# IOIO-OTG-v20.net
KiCad netlist of a schematic drawn in EAGLE
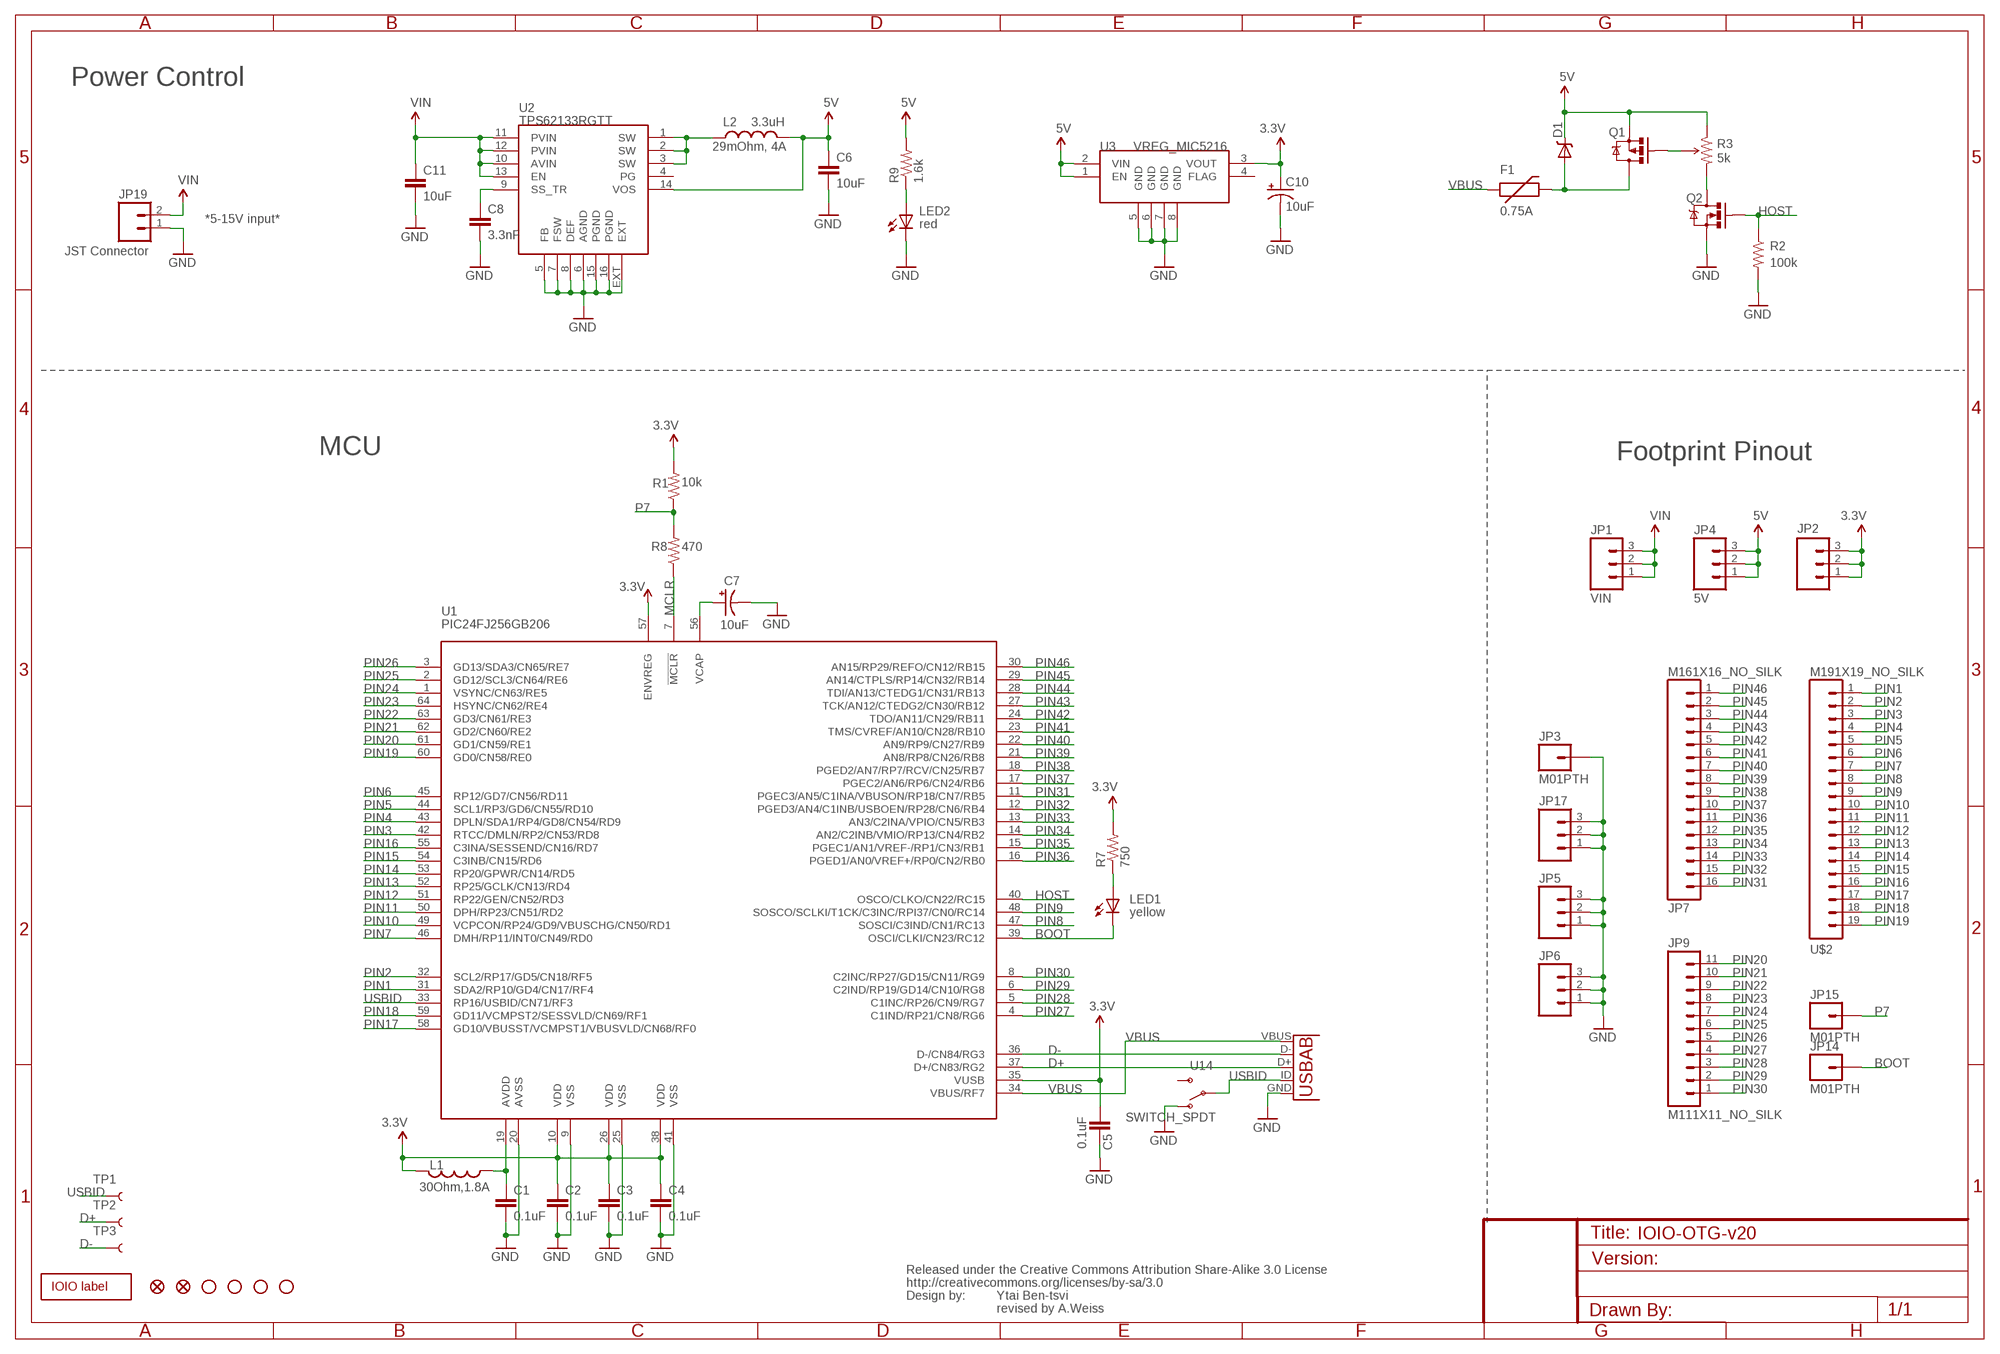
[diagram p0: schematic, sheet 1]

(export (version "E")
  (design (tool "Eeschema 10.0.6"))
  (components
    (comp (ref "C1")
      (value "0.1uF")
      (footprint "eagle-import:0402-CAP")
      (libsource (lib "eagle-import") (part "CAP0402-CAP"))
    )
    (comp (ref "C2")
      (value "0.1uF")
      (footprint "eagle-import:0402-CAP")
      (libsource (lib "eagle-import") (part "CAP0402-CAP"))
    )
    (comp (ref "C3")
      (value "0.1uF")
      (footprint "eagle-import:0402-CAP")
      (libsource (lib "eagle-import") (part "CAP0402-CAP"))
    )
    (comp (ref "C4")
      (value "0.1uF")
      (footprint "eagle-import:0402-CAP")
      (libsource (lib "eagle-import") (part "CAP0402-CAP"))
    )
    (comp (ref "C5")
      (value "0.1uF")
      (footprint "eagle-import:0402-CAP")
      (libsource (lib "eagle-import") (part "CAP0402-CAP"))
    )
    (comp (ref "C6")
      (value "10uF")
      (footprint "eagle-import:0805")
      (fields (field (name "PART#") "LMK212BJ106KG-T"))
      (libsource (lib "eagle-import") (part "SparkFun-Passives_CAP0805"))
    )
    (comp (ref "C7")
      (value "10uF")
      (footprint "eagle-import:EIA3216")
      (libsource (lib "eagle-import") (part "CAP_POL1206"))
    )
    (comp (ref "C8")
      (value "3.3nF")
      (footprint "eagle-import:0402-CAP")
      (libsource (lib "eagle-import") (part "CAP0402-CAP"))
    )
    (comp (ref "C10")
      (value "10uF")
      (footprint "eagle-import:EIA3216")
      (fields (field (name "PART#") "TAJA106K016RNJ"))
      (libsource (lib "eagle-import") (part "SparkFun-Passives_CAP_POL1206"))
    )
    (comp (ref "C11")
      (value "10uF")
      (footprint "eagle-import:1210")
      (fields (field (name "PART#") "UMK325C7106MM-T"))
      (libsource (lib "eagle-import") (part "SparkFun-Passives_CAP1210"))
    )
    (comp (ref "D1")
      (value "B340A")
      (footprint "eagle-import:SMA-DIODE")
      (fields (field (name "PART#") "B340A"))
      (libsource (lib "eagle-import") (part "DIODE-SCHOTTKY_"))
    )
    (comp (ref "F1")
      (value "PTCSMD")
      (footprint "eagle-import:PTC-1206")
      (fields (field (name "PART#") "0ZCA0075FF2G"))
      (libsource (lib "eagle-import") (part "PTCSMD"))
    )
    (comp (ref "JP1")
      (value "VIN")
      (footprint "eagle-import:1X03")
      (libsource (lib "eagle-import") (part "M03PTH"))
    )
    (comp (ref "JP2")
      (value "M03PTH")
      (footprint "eagle-import:1X03")
      (libsource (lib "eagle-import") (part "M03PTH"))
    )
    (comp (ref "JP3")
      (value "M01PTH")
      (footprint "eagle-import:1X01")
      (libsource (lib "eagle-import") (part "M01PTH"))
    )
    (comp (ref "JP4")
      (value "5V")
      (footprint "eagle-import:1X03")
      (libsource (lib "eagle-import") (part "M03PTH"))
    )
    (comp (ref "JP5")
      (value "M03PTH")
      (footprint "eagle-import:1X03")
      (libsource (lib "eagle-import") (part "M03PTH"))
    )
    (comp (ref "JP6")
      (value "M03PTH")
      (footprint "eagle-import:1X03")
      (libsource (lib "eagle-import") (part "M03PTH"))
    )
    (comp (ref "JP7")
      (value "M161X16_NO_SILK")
      (footprint "eagle-import:1X16_NO_SILK")
      (libsource (lib "eagle-import") (part "M161X16_NO_SILK"))
    )
    (comp (ref "JP8")
      (value "FIDUCIALUFIDUCIAL")
      (footprint "eagle-import:MICRO-FIDUCIAL")
      (libsource (lib "eagle-import") (part "FIDUCIALUFIDUCIAL"))
    )
    (comp (ref "JP9")
      (value "M111X11_NO_SILK")
      (footprint "eagle-import:1X11_NO_SILK")
      (libsource (lib "eagle-import") (part "M111X11_NO_SILK"))
    )
    (comp (ref "JP10")
      (value "STAND-OFF")
      (footprint "eagle-import:STAND-OFF")
      (libsource (lib "eagle-import") (part "STAND-OFF"))
    )
    (comp (ref "JP11")
      (value "STAND-OFF")
      (footprint "eagle-import:STAND-OFF")
      (libsource (lib "eagle-import") (part "STAND-OFF"))
    )
    (comp (ref "JP12")
      (value "STAND-OFF")
      (footprint "eagle-import:STAND-OFF")
      (libsource (lib "eagle-import") (part "STAND-OFF"))
    )
    (comp (ref "JP13")
      (value "STAND-OFF")
      (footprint "eagle-import:STAND-OFF")
      (libsource (lib "eagle-import") (part "STAND-OFF"))
    )
    (comp (ref "JP14")
      (value "M01PTH")
      (footprint "eagle-import:1X01")
      (libsource (lib "eagle-import") (part "M01PTH"))
    )
    (comp (ref "JP15")
      (value "M01PTH")
      (footprint "eagle-import:1X01")
      (libsource (lib "eagle-import") (part "M01PTH"))
    )
    (comp (ref "JP16")
      (value "FIDUCIALUFIDUCIAL")
      (footprint "eagle-import:MICRO-FIDUCIAL")
      (libsource (lib "eagle-import") (part "FIDUCIALUFIDUCIAL"))
    )
    (comp (ref "JP17")
      (value "M03PTH")
      (footprint "eagle-import:1X03")
      (libsource (lib "eagle-import") (part "M03PTH"))
    )
    (comp (ref "JP19")
      (value "JST Connector")
      (footprint "eagle-import:JST-2-SMD")
      (libsource (lib "eagle-import") (part "M02-JST-2MM-SMT"))
    )
    (comp (ref "L1")
      (value "30Ohm,1.8A")
      (footprint "eagle-import:C0402")
      (libsource (lib "eagle-import") (part "INDUCTOR0402"))
    )
    (comp (ref "L2")
      (value "VLC5045T-3R3N")
      (footprint "eagle-import:CR54")
      (fields (field (name "AM") "3.3uH"))
      (libsource (lib "eagle-import") (part "INDUCTORCR54"))
    )
    (comp (ref "LED1")
      (value "LY L29K-J1K2-26-Z")
      (footprint "eagle-import:LED-0603")
      (libsource (lib "eagle-import") (part "LED0603"))
    )
    (comp (ref "LED2")
      (value "LS L29K-G1J2-1-Z")
      (footprint "eagle-import:LED-0603")
      (libsource (lib "eagle-import") (part "LED0603"))
    )
    (comp (ref "Q1")
      (value "IRLML2244")
      (footprint "eagle-import:SOT23-3")
      (libsource (lib "eagle-import") (part "MOSFET-PCHANNELSMD"))
    )
    (comp (ref "Q2")
      (value "2N7002PW")
      (footprint "eagle-import:SOT323")
      (fields (field (name "PART#") "2N7002PW"))
      (libsource (lib "eagle-import") (part "MOSFET-NCHANNELSOT323"))
    )
    (comp (ref "R1")
      (value "10k")
      (footprint "eagle-import:0402-RES")
      (libsource (lib "eagle-import") (part "RESISTOR0402-RES"))
    )
    (comp (ref "R2")
      (value "100k")
      (footprint "eagle-import:0402-RES")
      (libsource (lib "eagle-import") (part "RESISTOR0402-RES"))
    )
    (comp (ref "R3")
      (value "TS53YL502MR10")
      (footprint "eagle-import:TRIMPOT-5MM")
      (fields (field (name "PART#") "TS53YL502MR10"))
      (libsource (lib "eagle-import") (part "TRIMPOTTRIMPOT-5MM"))
    )
    (comp (ref "R7")
      (value "750")
      (footprint "eagle-import:0402-RES")
      (libsource (lib "eagle-import") (part "RESISTOR0402-RES"))
    )
    (comp (ref "R8")
      (value "470")
      (footprint "eagle-import:0402-RES")
      (libsource (lib "eagle-import") (part "RESISTOR0402-RES"))
    )
    (comp (ref "R9")
      (value "1.6k")
      (footprint "eagle-import:0402-RES")
      (libsource (lib "eagle-import") (part "RESISTOR0402-RES"))
    )
    (comp (ref "TP1")
      (value "TEST-POINT3")
      (footprint "eagle-import:PAD.03X.03")
      (libsource (lib "eagle-import") (part "TEST-POINT3"))
    )
    (comp (ref "TP2")
      (value "TEST-POINT3")
      (footprint "eagle-import:PAD.03X.03")
      (libsource (lib "eagle-import") (part "TEST-POINT3"))
    )
    (comp (ref "TP3")
      (value "TEST-POINT3")
      (footprint "eagle-import:PAD.03X.03")
      (libsource (lib "eagle-import") (part "TEST-POINT3"))
    )
    (comp (ref "U$1")
      (value "CREATIVE_COMMONS")
      (footprint "eagle-import:CREATIVE_COMMONS")
      (libsource (lib "eagle-import") (part "CREATIVE_COMMONS"))
    )
    (comp (ref "U$2")
      (value "M191X19_NO_SILK")
      (footprint "eagle-import:1X19_NO_SILK")
      (libsource (lib "eagle-import") (part "M191X19_NO_SILK"))
    )
    (comp (ref "U$3")
      (value "10104111-0001LF")
      (footprint "eagle-import:USB-AB-MICRO-SMD")
      (libsource (lib "eagle-import") (part "USB_AB"))
    )
    (comp (ref "U$6")
      (value "IOIO-OTG")
      (footprint "eagle-import:IOIO-OTG-COPPER-EXPOSED")
      (libsource (lib "eagle-import") (part "IOIO-OTG"))
    )
    (comp (ref "U1")
      (value "PIC24FJ256GB206")
      (footprint "eagle-import:PIC24FXXX_TQFP64")
      (libsource (lib "eagle-import") (part "PIC24FXXXDAX06"))
    )
    (comp (ref "U2")
      (value "TPS62133RGTT")
      (footprint "eagle-import:QFN16-3X3MM")
      (libsource (lib "eagle-import") (part "TPS6214X"))
    )
    (comp (ref "U3")
      (value "VREG_MIC5216")
      (footprint "eagle-import:MSOP8")
      (libsource (lib "eagle-import") (part "VREG_MIC5216"))
    )
    (comp (ref "U14")
      (value "SWITCH_SPDT")
      (footprint "eagle-import:KPS-1290")
      (libsource (lib "eagle-import") (part "SWITCH_SPDT"))
    )
  )
  (nets
    (net (code "1") (name "/BOOT") (class "Default")
      (node (ref "JP14") (pin "1") (pinfunction "1_1") (pintype "passive"))
      (node (ref "LED1") (pin "C") (pinfunction "C_C") (pintype "passive"))
      (node (ref "U1") (pin "39") (pinfunction "OSCI/CLKI/CN23/RC12_39") (pintype "bidirectional"))
    )
    (net (code "2") (name "/D+") (class "Default")
      (node (ref "TP2") (pin "P$1") (pinfunction "1_P$1") (pintype "bidirectional"))
      (node (ref "U$3") (pin "D+") (pinfunction "D+_D+") (pintype "bidirectional"))
      (node (ref "U1") (pin "37") (pinfunction "D+/CN83/RG2_37") (pintype "bidirectional"))
    )
    (net (code "3") (name "/D-") (class "Default")
      (node (ref "TP3") (pin "P$1") (pinfunction "1_P$1") (pintype "bidirectional"))
      (node (ref "U$3") (pin "D-") (pinfunction "D-_D-") (pintype "bidirectional"))
      (node (ref "U1") (pin "36") (pinfunction "D-/CN84/RG3_36") (pintype "bidirectional"))
    )
    (net (code "4") (name "/HOST") (class "Default")
      (node (ref "Q2") (pin "1") (pinfunction "G_1") (pintype "passive"))
      (node (ref "R2") (pin "1") (pinfunction "1_1") (pintype "passive"))
      (node (ref "U1") (pin "40") (pinfunction "OSCO/CLKO/CN22/RC15_40") (pintype "bidirectional"))
    )
    (net (code "5") (name "/MCLR") (class "Default")
      (node (ref "R8") (pin "1") (pinfunction "1_1") (pintype "passive"))
      (node (ref "U1") (pin "7") (pinfunction "~{MCLR}_7") (pintype "input"))
    )
    (net (code "6") (name "/P7") (class "Default")
      (node (ref "JP15") (pin "1") (pinfunction "1_1") (pintype "passive"))
      (node (ref "R1") (pin "1") (pinfunction "1_1") (pintype "passive"))
      (node (ref "R8") (pin "2") (pinfunction "2_2") (pintype "passive"))
    )
    (net (code "7") (name "/PIN1") (class "Default")
      (node (ref "U$2") (pin "1") (pinfunction "1_1") (pintype "passive"))
      (node (ref "U1") (pin "31") (pinfunction "SDA2/RP10/GD4/CN17/RF4_31") (pintype "bidirectional"))
    )
    (net (code "8") (name "/PIN2") (class "Default")
      (node (ref "U$2") (pin "2") (pinfunction "2_2") (pintype "passive"))
      (node (ref "U1") (pin "32") (pinfunction "SCL2/RP17/GD5/CN18/RF5_32") (pintype "bidirectional"))
    )
    (net (code "9") (name "/PIN3") (class "Default")
      (node (ref "U$2") (pin "3") (pinfunction "3_3") (pintype "passive"))
      (node (ref "U1") (pin "42") (pinfunction "RTCC/DMLN/RP2/CN53/RD8_42") (pintype "bidirectional"))
    )
    (net (code "10") (name "/PIN4") (class "Default")
      (node (ref "U$2") (pin "4") (pinfunction "4_4") (pintype "passive"))
      (node (ref "U1") (pin "43") (pinfunction "DPLN/SDA1/RP4/GD8/CN54/RD9_43") (pintype "bidirectional"))
    )
    (net (code "11") (name "/PIN5") (class "Default")
      (node (ref "U$2") (pin "5") (pinfunction "5_5") (pintype "passive"))
      (node (ref "U1") (pin "44") (pinfunction "SCL1/RP3/GD6/CN55/RD10_44") (pintype "bidirectional"))
    )
    (net (code "12") (name "/PIN6") (class "Default")
      (node (ref "U$2") (pin "6") (pinfunction "6_6") (pintype "passive"))
      (node (ref "U1") (pin "45") (pinfunction "RP12/GD7/CN56/RD11_45") (pintype "bidirectional"))
    )
    (net (code "13") (name "/PIN7") (class "Default")
      (node (ref "U$2") (pin "7") (pinfunction "7_7") (pintype "passive"))
      (node (ref "U1") (pin "46") (pinfunction "DMH/RP11/INT0/CN49/RD0_46") (pintype "bidirectional"))
    )
    (net (code "14") (name "/PIN8") (class "Default")
      (node (ref "U$2") (pin "8") (pinfunction "8_8") (pintype "passive"))
      (node (ref "U1") (pin "47") (pinfunction "SOSCI/C3IND/CN1/RC13_47") (pintype "bidirectional"))
    )
    (net (code "15") (name "/PIN9") (class "Default")
      (node (ref "U$2") (pin "9") (pinfunction "9_9") (pintype "passive"))
      (node (ref "U1") (pin "48") (pinfunction "SOSCO/SCLKI/T1CK/C3INC/RPI37/CN0/RC14_48") (pintype "bidirectional"))
    )
    (net (code "16") (name "/PIN10") (class "Default")
      (node (ref "U$2") (pin "10") (pinfunction "10_10") (pintype "passive"))
      (node (ref "U1") (pin "49") (pinfunction "VCPCON/RP24/GD9/VBUSCHG/CN50/RD1_49") (pintype "bidirectional"))
    )
    (net (code "17") (name "/PIN11") (class "Default")
      (node (ref "U$2") (pin "11") (pinfunction "11_11") (pintype "passive"))
      (node (ref "U1") (pin "50") (pinfunction "DPH/RP23/CN51/RD2_50") (pintype "bidirectional"))
    )
    (net (code "18") (name "/PIN12") (class "Default")
      (node (ref "U$2") (pin "12") (pinfunction "12_12") (pintype "passive"))
      (node (ref "U1") (pin "51") (pinfunction "RP22/GEN/CN52/RD3_51") (pintype "bidirectional"))
    )
    (net (code "19") (name "/PIN13") (class "Default")
      (node (ref "U$2") (pin "13") (pinfunction "13_13") (pintype "passive"))
      (node (ref "U1") (pin "52") (pinfunction "RP25/GCLK/CN13/RD4_52") (pintype "bidirectional"))
    )
    (net (code "20") (name "/PIN14") (class "Default")
      (node (ref "U$2") (pin "14") (pinfunction "14_14") (pintype "passive"))
      (node (ref "U1") (pin "53") (pinfunction "RP20/GPWR/CN14/RD5_53") (pintype "bidirectional"))
    )
    (net (code "21") (name "/PIN15") (class "Default")
      (node (ref "U$2") (pin "15") (pinfunction "15_15") (pintype "passive"))
      (node (ref "U1") (pin "54") (pinfunction "C3INB/CN15/RD6_54") (pintype "bidirectional"))
    )
    (net (code "22") (name "/PIN16") (class "Default")
      (node (ref "U$2") (pin "16") (pinfunction "16_16") (pintype "passive"))
      (node (ref "U1") (pin "55") (pinfunction "C3INA/SESSEND/CN16/RD7_55") (pintype "bidirectional"))
    )
    (net (code "23") (name "/PIN17") (class "Default")
      (node (ref "U$2") (pin "17") (pinfunction "17_17") (pintype "passive"))
      (node (ref "U1") (pin "58") (pinfunction "GD10/VBUSST/VCMPST1/VBUSVLD/CN68/RF0_58") (pintype "bidirectional"))
    )
    (net (code "24") (name "/PIN18") (class "Default")
      (node (ref "U$2") (pin "18") (pinfunction "18_18") (pintype "passive"))
      (node (ref "U1") (pin "59") (pinfunction "GD11/VCMPST2/SESSVLD/CN69/RF1_59") (pintype "bidirectional"))
    )
    (net (code "25") (name "/PIN19") (class "Default")
      (node (ref "U$2") (pin "19") (pinfunction "19_19") (pintype "passive"))
      (node (ref "U1") (pin "60") (pinfunction "GD0/CN58/RE0_60") (pintype "bidirectional"))
    )
    (net (code "26") (name "/PIN20") (class "Default")
      (node (ref "JP9") (pin "11") (pinfunction "11_11") (pintype "passive"))
      (node (ref "U1") (pin "61") (pinfunction "GD1/CN59/RE1_61") (pintype "bidirectional"))
    )
    (net (code "27") (name "/PIN21") (class "Default")
      (node (ref "JP9") (pin "10") (pinfunction "10_10") (pintype "passive"))
      (node (ref "U1") (pin "62") (pinfunction "GD2/CN60/RE2_62") (pintype "bidirectional"))
    )
    (net (code "28") (name "/PIN22") (class "Default")
      (node (ref "JP9") (pin "9") (pinfunction "9_9") (pintype "passive"))
      (node (ref "U1") (pin "63") (pinfunction "GD3/CN61/RE3_63") (pintype "bidirectional"))
    )
    (net (code "29") (name "/PIN23") (class "Default")
      (node (ref "JP9") (pin "8") (pinfunction "8_8") (pintype "passive"))
      (node (ref "U1") (pin "64") (pinfunction "HSYNC/CN62/RE4_64") (pintype "bidirectional"))
    )
    (net (code "30") (name "/PIN24") (class "Default")
      (node (ref "JP9") (pin "7") (pinfunction "7_7") (pintype "passive"))
      (node (ref "U1") (pin "1") (pinfunction "VSYNC/CN63/RE5_1") (pintype "bidirectional"))
    )
    (net (code "31") (name "/PIN25") (class "Default")
      (node (ref "JP9") (pin "6") (pinfunction "6_6") (pintype "passive"))
      (node (ref "U1") (pin "2") (pinfunction "GD12/SCL3/CN64/RE6_2") (pintype "bidirectional"))
    )
    (net (code "32") (name "/PIN26") (class "Default")
      (node (ref "JP9") (pin "5") (pinfunction "5_5") (pintype "passive"))
      (node (ref "U1") (pin "3") (pinfunction "GD13/SDA3/CN65/RE7_3") (pintype "bidirectional"))
    )
    (net (code "33") (name "/PIN27") (class "Default")
      (node (ref "JP9") (pin "4") (pinfunction "4_4") (pintype "passive"))
      (node (ref "U1") (pin "4") (pinfunction "C1IND/RP21/CN8/RG6_4") (pintype "bidirectional"))
    )
    (net (code "34") (name "/PIN28") (class "Default")
      (node (ref "JP9") (pin "3") (pinfunction "3_3") (pintype "passive"))
      (node (ref "U1") (pin "5") (pinfunction "C1INC/RP26/CN9/RG7_5") (pintype "bidirectional"))
    )
    (net (code "35") (name "/PIN29") (class "Default")
      (node (ref "JP9") (pin "2") (pinfunction "2_2") (pintype "passive"))
      (node (ref "U1") (pin "6") (pinfunction "C2IND/RP19/GD14/CN10/RG8_6") (pintype "bidirectional"))
    )
    (net (code "36") (name "/PIN30") (class "Default")
      (node (ref "JP9") (pin "1") (pinfunction "1_1") (pintype "passive"))
      (node (ref "U1") (pin "8") (pinfunction "C2INC/RP27/GD15/CN11/RG9_8") (pintype "bidirectional"))
    )
    (net (code "37") (name "/PIN31") (class "Default")
      (node (ref "JP7") (pin "16") (pinfunction "16_16") (pintype "passive"))
      (node (ref "U1") (pin "11") (pinfunction "PGEC3/AN5/C1INA/VBUSON/RP18/CN7/RB5_11") (pintype "bidirectional"))
    )
    (net (code "38") (name "/PIN32") (class "Default")
      (node (ref "JP7") (pin "15") (pinfunction "15_15") (pintype "passive"))
      (node (ref "U1") (pin "12") (pinfunction "PGED3/AN4/C1INB/USBOEN/RP28/CN6/RB4_12") (pintype "bidirectional"))
    )
    (net (code "39") (name "/PIN33") (class "Default")
      (node (ref "JP7") (pin "14") (pinfunction "14_14") (pintype "passive"))
      (node (ref "U1") (pin "13") (pinfunction "AN3/C2INA/VPIO/CN5/RB3_13") (pintype "bidirectional"))
    )
    (net (code "40") (name "/PIN34") (class "Default")
      (node (ref "JP7") (pin "13") (pinfunction "13_13") (pintype "passive"))
      (node (ref "U1") (pin "14") (pinfunction "AN2/C2INB/VMIO/RP13/CN4/RB2_14") (pintype "bidirectional"))
    )
    (net (code "41") (name "/PIN35") (class "Default")
      (node (ref "JP7") (pin "12") (pinfunction "12_12") (pintype "passive"))
      (node (ref "U1") (pin "15") (pinfunction "PGEC1/AN1/VREF-/RP1/CN3/RB1_15") (pintype "bidirectional"))
    )
    (net (code "42") (name "/PIN36") (class "Default")
      (node (ref "JP7") (pin "11") (pinfunction "11_11") (pintype "passive"))
      (node (ref "U1") (pin "16") (pinfunction "PGED1/AN0/VREF+/RP0/CN2/RB0_16") (pintype "bidirectional"))
    )
    (net (code "43") (name "/PIN37") (class "Default")
      (node (ref "JP7") (pin "10") (pinfunction "10_10") (pintype "passive"))
      (node (ref "U1") (pin "17") (pinfunction "PGEC2/AN6/RP6/CN24/RB6_17") (pintype "bidirectional"))
    )
    (net (code "44") (name "/PIN38") (class "Default")
      (node (ref "JP7") (pin "9") (pinfunction "9_9") (pintype "passive"))
      (node (ref "U1") (pin "18") (pinfunction "PGED2/AN7/RP7/RCV/CN25/RB7_18") (pintype "bidirectional"))
    )
    (net (code "45") (name "/PIN39") (class "Default")
      (node (ref "JP7") (pin "8") (pinfunction "8_8") (pintype "passive"))
      (node (ref "U1") (pin "21") (pinfunction "AN8/RP8/CN26/RB8_21") (pintype "bidirectional"))
    )
    (net (code "46") (name "/PIN40") (class "Default")
      (node (ref "JP7") (pin "7") (pinfunction "7_7") (pintype "passive"))
      (node (ref "U1") (pin "22") (pinfunction "AN9/RP9/CN27/RB9_22") (pintype "bidirectional"))
    )
    (net (code "47") (name "/PIN41") (class "Default")
      (node (ref "JP7") (pin "6") (pinfunction "6_6") (pintype "passive"))
      (node (ref "U1") (pin "23") (pinfunction "TMS/CVREF/AN10/CN28/RB10_23") (pintype "bidirectional"))
    )
    (net (code "48") (name "/PIN42") (class "Default")
      (node (ref "JP7") (pin "5") (pinfunction "5_5") (pintype "passive"))
      (node (ref "U1") (pin "24") (pinfunction "TDO/AN11/CN29/RB11_24") (pintype "bidirectional"))
    )
    (net (code "49") (name "/PIN43") (class "Default")
      (node (ref "JP7") (pin "4") (pinfunction "4_4") (pintype "passive"))
      (node (ref "U1") (pin "27") (pinfunction "TCK/AN12/CTEDG2/CN30/RB12_27") (pintype "bidirectional"))
    )
    (net (code "50") (name "/PIN44") (class "Default")
      (node (ref "JP7") (pin "3") (pinfunction "3_3") (pintype "passive"))
      (node (ref "U1") (pin "28") (pinfunction "TDI/AN13/CTEDG1/CN31/RB13_28") (pintype "bidirectional"))
    )
    (net (code "51") (name "/PIN45") (class "Default")
      (node (ref "JP7") (pin "2") (pinfunction "2_2") (pintype "passive"))
      (node (ref "U1") (pin "29") (pinfunction "AN14/CTPLS/RP14/CN32/RB14_29") (pintype "bidirectional"))
    )
    (net (code "52") (name "/PIN46") (class "Default")
      (node (ref "JP7") (pin "1") (pinfunction "1_1") (pintype "passive"))
      (node (ref "U1") (pin "30") (pinfunction "AN15/RP29/REFO/CN12/RB15_30") (pintype "bidirectional"))
    )
    (net (code "53") (name "/USBID") (class "Default")
      (node (ref "TP1") (pin "P$1") (pinfunction "1_P$1") (pintype "bidirectional"))
      (node (ref "U$3") (pin "ID") (pinfunction "USBID_ID") (pintype "bidirectional"))
      (node (ref "U1") (pin "33") (pinfunction "RP16/USBID/CN71/RF3_33") (pintype "bidirectional"))
      (node (ref "U14") (pin "P") (pinfunction "P_P") (pintype "passive"))
    )
    (net (code "54") (name "/VBUS") (class "Default")
      (node (ref "F1") (pin "1") (pinfunction "1_1") (pintype "bidirectional"))
      (node (ref "U$3") (pin "VBUS") (pinfunction "VBUS_VBUS") (pintype "bidirectional"))
      (node (ref "U1") (pin "34") (pinfunction "VBUS/RF7_34") (pintype "input"))
    )
    (net (code "55") (name "3.3V") (class "Default")
      (node (ref "C10") (pin "A") (pinfunction "+_A") (pintype "passive"))
      (node (ref "C2") (pin "1") (pinfunction "1_1") (pintype "passive"))
      (node (ref "C3") (pin "1") (pinfunction "1_1") (pintype "passive"))
      (node (ref "C4") (pin "1") (pinfunction "1_1") (pintype "passive"))
      (node (ref "C5") (pin "1") (pinfunction "1_1") (pintype "passive"))
      (node (ref "JP2") (pin "1") (pinfunction "1_1") (pintype "passive"))
      (node (ref "JP2") (pin "2") (pinfunction "2_2") (pintype "passive"))
      (node (ref "JP2") (pin "3") (pinfunction "3_3") (pintype "passive"))
      (node (ref "L1") (pin "2") (pinfunction "2_2") (pintype "passive"))
      (node (ref "R1") (pin "2") (pinfunction "2_2") (pintype "passive"))
      (node (ref "R7") (pin "2") (pinfunction "2_2") (pintype "passive"))
      (node (ref "U1") (pin "10") (pinfunction "VDD_10") (pintype "power_in"))
      (node (ref "U1") (pin "26") (pinfunction "VDD_26") (pintype "power_in"))
      (node (ref "U1") (pin "35") (pinfunction "VUSB_35") (pintype "power_in"))
      (node (ref "U1") (pin "38") (pinfunction "VDD_38") (pintype "power_in"))
      (node (ref "U1") (pin "57") (pinfunction "ENVREG_57") (pintype "input"))
      (node (ref "U3") (pin "3") (pinfunction "VOUT_3") (pintype "bidirectional"))
    )
    (net (code "56") (name "5V") (class "Default")
      (node (ref "C6") (pin "1") (pinfunction "1_1") (pintype "passive"))
      (node (ref "D1") (pin "C") (pinfunction "C_C") (pintype "passive"))
      (node (ref "JP4") (pin "1") (pinfunction "1_1") (pintype "passive"))
      (node (ref "JP4") (pin "2") (pinfunction "2_2") (pintype "passive"))
      (node (ref "JP4") (pin "3") (pinfunction "3_3") (pintype "passive"))
      (node (ref "L2") (pin "P$2") (pinfunction "2_P$2") (pintype "passive"))
      (node (ref "Q1") (pin "2") (pinfunction "S_2") (pintype "passive"))
      (node (ref "R3") (pin "A") (pinfunction "CCW_A") (pintype "passive"))
      (node (ref "R9") (pin "2") (pinfunction "2_2") (pintype "passive"))
      (node (ref "U2") (pin "14") (pinfunction "VOS_14") (pintype "bidirectional"))
      (node (ref "U3") (pin "1") (pinfunction "EN_1") (pintype "bidirectional"))
      (node (ref "U3") (pin "2") (pinfunction "VIN_2") (pintype "bidirectional"))
    )
    (net (code "57") (name "GND") (class "Default")
      (node (ref "C1") (pin "2") (pinfunction "2_2") (pintype "passive"))
      (node (ref "C10") (pin "C") (pinfunction "-_C") (pintype "passive"))
      (node (ref "C11") (pin "2") (pinfunction "2_2") (pintype "passive"))
      (node (ref "C2") (pin "2") (pinfunction "2_2") (pintype "passive"))
      (node (ref "C3") (pin "2") (pinfunction "2_2") (pintype "passive"))
      (node (ref "C4") (pin "2") (pinfunction "2_2") (pintype "passive"))
      (node (ref "C5") (pin "2") (pinfunction "2_2") (pintype "passive"))
      (node (ref "C6") (pin "2") (pinfunction "2_2") (pintype "passive"))
      (node (ref "C7") (pin "C") (pinfunction "-_C") (pintype "passive"))
      (node (ref "C8") (pin "2") (pinfunction "2_2") (pintype "passive"))
      (node (ref "JP17") (pin "1") (pinfunction "1_1") (pintype "passive"))
      (node (ref "JP17") (pin "2") (pinfunction "2_2") (pintype "passive"))
      (node (ref "JP17") (pin "3") (pinfunction "3_3") (pintype "passive"))
      (node (ref "JP19") (pin "1") (pinfunction "1_1") (pintype "passive"))
      (node (ref "JP3") (pin "1") (pinfunction "1_1") (pintype "passive"))
      (node (ref "JP5") (pin "1") (pinfunction "1_1") (pintype "passive"))
      (node (ref "JP5") (pin "2") (pinfunction "2_2") (pintype "passive"))
      (node (ref "JP5") (pin "3") (pinfunction "3_3") (pintype "passive"))
      (node (ref "JP6") (pin "1") (pinfunction "1_1") (pintype "passive"))
      (node (ref "JP6") (pin "2") (pinfunction "2_2") (pintype "passive"))
      (node (ref "JP6") (pin "3") (pinfunction "3_3") (pintype "passive"))
      (node (ref "LED2") (pin "C") (pinfunction "C_C") (pintype "passive"))
      (node (ref "Q2") (pin "2") (pinfunction "S_2") (pintype "passive"))
      (node (ref "R2") (pin "2") (pinfunction "2_2") (pintype "passive"))
      (node (ref "U$3") (pin "GND") (pinfunction "GND_GND") (pintype "bidirectional"))
      (node (ref "U1") (pin "20") (pinfunction "AVSS_20") (pintype "power_in"))
      (node (ref "U1") (pin "25") (pinfunction "VSS_25") (pintype "power_in"))
      (node (ref "U1") (pin "41") (pinfunction "VSS_41") (pintype "power_in"))
      (node (ref "U1") (pin "9") (pinfunction "VSS_9") (pintype "power_in"))
      (node (ref "U14") (pin "O") (pinfunction "O_O") (pintype "passive"))
      (node (ref "U2") (pin "15") (pinfunction "PGND_15") (pintype "bidirectional"))
      (node (ref "U2") (pin "16") (pinfunction "PGND_16") (pintype "bidirectional"))
      (node (ref "U2") (pin "5") (pinfunction "FB_5") (pintype "bidirectional"))
      (node (ref "U2") (pin "6") (pinfunction "AGND_6") (pintype "bidirectional"))
      (node (ref "U2") (pin "7") (pinfunction "FSW_7") (pintype "bidirectional"))
      (node (ref "U2") (pin "8") (pinfunction "DEF_8") (pintype "bidirectional"))
      (node (ref "U2") (pin "EXT") (pinfunction "EXT_EXT") (pintype "bidirectional"))
      (node (ref "U3") (pin "5") (pinfunction "GND_5") (pintype "bidirectional"))
      (node (ref "U3") (pin "6") (pinfunction "GND_6") (pintype "bidirectional"))
      (node (ref "U3") (pin "7") (pinfunction "GND_7") (pintype "bidirectional"))
      (node (ref "U3") (pin "8") (pinfunction "GND_8") (pintype "bidirectional"))
    )
    (net (code "58") (name "Net-(C7-+)") (class "Default")
      (node (ref "C7") (pin "A") (pinfunction "+_A") (pintype "passive"))
      (node (ref "U1") (pin "56") (pinfunction "VCAP_56") (pintype "power_in"))
    )
    (net (code "59") (name "Net-(L2-1)") (class "Default")
      (node (ref "L2") (pin "P$1") (pinfunction "1_P$1") (pintype "passive"))
      (node (ref "U2") (pin "1") (pinfunction "SW_1") (pintype "bidirectional"))
      (node (ref "U2") (pin "2") (pinfunction "SW_2") (pintype "bidirectional"))
      (node (ref "U2") (pin "3") (pinfunction "SW_3") (pintype "bidirectional"))
    )
    (net (code "60") (name "Net-(LED1-PadA)") (class "Default")
      (node (ref "LED1") (pin "A") (pinfunction "A_A") (pintype "passive"))
      (node (ref "R7") (pin "1") (pinfunction "1_1") (pintype "passive"))
    )
    (net (code "61") (name "Net-(LED2-PadA)") (class "Default")
      (node (ref "LED2") (pin "A") (pinfunction "A_A") (pintype "passive"))
      (node (ref "R9") (pin "1") (pinfunction "1_1") (pintype "passive"))
    )
    (net (code "62") (name "Net-(Q1-D)") (class "Default")
      (node (ref "D1") (pin "A") (pinfunction "A_A") (pintype "passive"))
      (node (ref "F1") (pin "2") (pinfunction "2_2") (pintype "bidirectional"))
      (node (ref "Q1") (pin "3") (pinfunction "D_3") (pintype "passive"))
    )
    (net (code "63") (name "Net-(Q1-G)") (class "Default")
      (node (ref "Q1") (pin "1") (pinfunction "G_1") (pintype "passive"))
      (node (ref "R3") (pin "B") (pinfunction "WIPER_B") (pintype "passive"))
    )
    (net (code "64") (name "Net-(Q2-D)") (class "Default")
      (node (ref "Q2") (pin "3") (pinfunction "D_3") (pintype "passive"))
      (node (ref "R3") (pin "C") (pinfunction "CW_C") (pintype "passive"))
    )
    (net (code "65") (name "Net-(U1-AVDD)") (class "Default")
      (node (ref "C1") (pin "1") (pinfunction "1_1") (pintype "passive"))
      (node (ref "L1") (pin "1") (pinfunction "1_1") (pintype "passive"))
      (node (ref "U1") (pin "19") (pinfunction "AVDD_19") (pintype "power_in"))
    )
    (net (code "66") (name "Net-(U2-SS_TR)") (class "Default")
      (node (ref "C8") (pin "1") (pinfunction "1_1") (pintype "passive"))
      (node (ref "U2") (pin "9") (pinfunction "SS_TR_9") (pintype "bidirectional"))
    )
    (net (code "67") (name "VIN") (class "Default")
      (node (ref "C11") (pin "1") (pinfunction "1_1") (pintype "passive"))
      (node (ref "JP1") (pin "1") (pinfunction "1_1") (pintype "passive"))
      (node (ref "JP1") (pin "2") (pinfunction "2_2") (pintype "passive"))
      (node (ref "JP1") (pin "3") (pinfunction "3_3") (pintype "passive"))
      (node (ref "JP19") (pin "2") (pinfunction "2_2") (pintype "passive"))
      (node (ref "U2") (pin "10") (pinfunction "AVIN_10") (pintype "bidirectional"))
      (node (ref "U2") (pin "11") (pinfunction "PVIN_11") (pintype "bidirectional"))
      (node (ref "U2") (pin "12") (pinfunction "PVIN_12") (pintype "bidirectional"))
      (node (ref "U2") (pin "13") (pinfunction "EN_13") (pintype "bidirectional"))
    )
    (net (code "68") (name "unconnected-(U2-PG-Pad4)") (class "Default")
      (node (ref "U2") (pin "4") (pinfunction "PG_4") (pintype "bidirectional"))
    )
    (net (code "69") (name "unconnected-(U3-FLAG-Pad4)") (class "Default")
      (node (ref "U3") (pin "4") (pinfunction "FLAG_4") (pintype "bidirectional"))
    )
    (net (code "70") (name "unconnected-(U14-PadS)") (class "Default")
      (node (ref "U14") (pin "S") (pinfunction "S_S") (pintype "passive"))
    )
  )
)
